# wirelessSensor_0_1.net
KiCad netlist of a schematic drawn in EAGLE
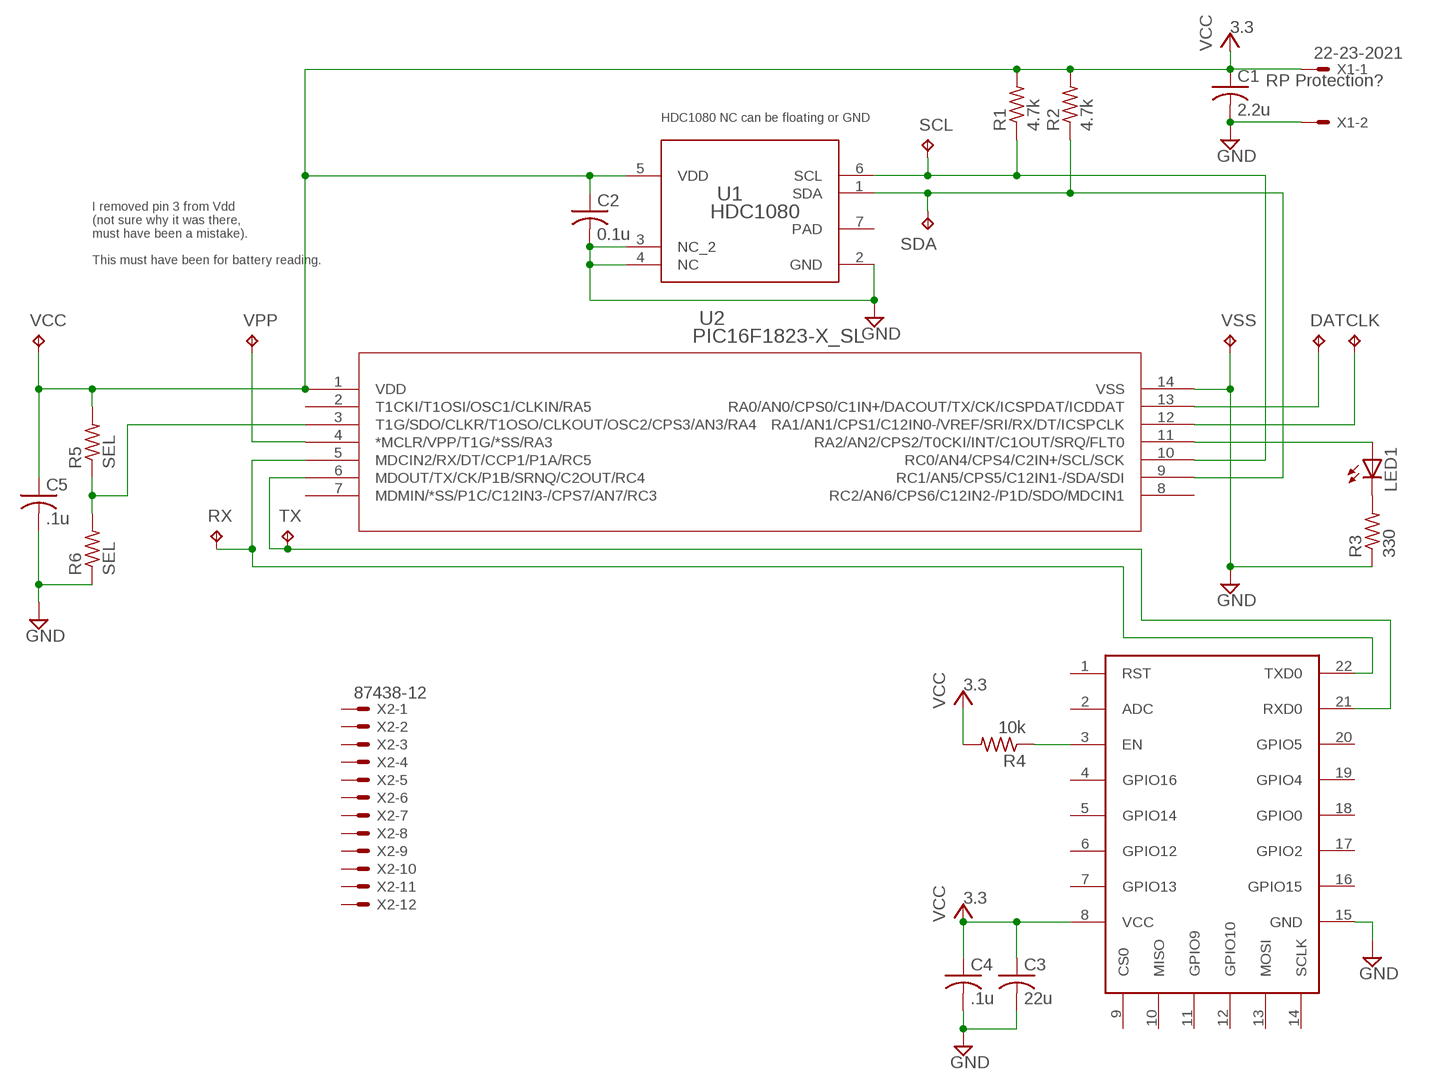
[diagram p0: schematic, sheet 1]

(export (version "E")
  (design (tool "Eeschema 10.0.6"))
  (components
    (comp (ref "C1")
      (value "2.2u")
      (footprint "eagle-import:C0603")
      (libsource (lib "eagle-import") (part "C-USC0603"))
    )
    (comp (ref "C2")
      (value "0.1u")
      (footprint "eagle-import:C0603")
      (libsource (lib "eagle-import") (part "C-USC0603"))
    )
    (comp (ref "C3")
      (value "22u")
      (footprint "eagle-import:C0603K")
      (libsource (lib "eagle-import") (part "C-USC0603K"))
    )
    (comp (ref "C4")
      (value ".1u")
      (footprint "eagle-import:C0603K")
      (libsource (lib "eagle-import") (part "C-USC0603K"))
    )
    (comp (ref "C5")
      (value ".1u")
      (footprint "eagle-import:C0603K")
      (libsource (lib "eagle-import") (part "C-USC0603K"))
    )
    (comp (ref "CLK")
      (value "TPB1,27")
      (footprint "eagle-import:B1,27")
      (libsource (lib "eagle-import") (part "TPB1,27"))
    )
    (comp (ref "DAT")
      (value "TPB1,27")
      (footprint "eagle-import:B1,27")
      (libsource (lib "eagle-import") (part "TPB1,27"))
    )
    (comp (ref "LED1")
      (value "LEDCHIP-LED0603")
      (footprint "eagle-import:CHIP-LED0603")
      (libsource (lib "eagle-import") (part "LEDCHIP-LED0603"))
    )
    (comp (ref "R1")
      (value "4.7k")
      (footprint "eagle-import:R0603")
      (libsource (lib "eagle-import") (part "R-US_R0603"))
    )
    (comp (ref "R2")
      (value "4.7k")
      (footprint "eagle-import:R0603")
      (libsource (lib "eagle-import") (part "R-US_R0603"))
    )
    (comp (ref "R3")
      (value "330")
      (footprint "eagle-import:R0603")
      (libsource (lib "eagle-import") (part "R-US_R0603"))
    )
    (comp (ref "R4")
      (value "10k")
      (footprint "eagle-import:R0603")
      (libsource (lib "eagle-import") (part "R-US_R0603"))
    )
    (comp (ref "R5")
      (value "SEL")
      (footprint "eagle-import:R0603")
      (libsource (lib "eagle-import") (part "R-US_R0603"))
    )
    (comp (ref "R6")
      (value "SEL")
      (footprint "eagle-import:R0603")
      (libsource (lib "eagle-import") (part "R-US_R0603"))
    )
    (comp (ref "RX")
      (value "TPB1,27")
      (footprint "eagle-import:B1,27")
      (libsource (lib "eagle-import") (part "TPB1,27"))
    )
    (comp (ref "SCL")
      (value "TPB1,27")
      (footprint "eagle-import:B1,27")
      (libsource (lib "eagle-import") (part "TPB1,27"))
    )
    (comp (ref "SDA")
      (value "TPB1,27")
      (footprint "eagle-import:B1,27")
      (libsource (lib "eagle-import") (part "TPB1,27"))
    )
    (comp (ref "TX")
      (value "TPB1,27")
      (footprint "eagle-import:B1,27")
      (libsource (lib "eagle-import") (part "TPB1,27"))
    )
    (comp (ref "U$1")
      (value "ESP8266-12E")
      (footprint "eagle-import:ESP8266-12E")
      (libsource (lib "eagle-import") (part "ESP8266-12E"))
    )
    (comp (ref "U1")
      (value "HDC1080")
      (footprint "eagle-import:DMB0006A")
      (fields
        (field (name "ALTERNATEPARTNUMBER") "HDC1080DMBT")
        (field (name "MANUFACTURER") "Texas Instruments")
        (field (name "PARTNUMBER") "HDC1080DMBR")
      )
      (libsource (lib "eagle-import") (part "HDC1080DMBR"))
    )
    (comp (ref "U2")
      (value "PIC16F1823-X_SL")
      (footprint "eagle-import:SOIC14-N_MC")
      (libsource (lib "eagle-import") (part "PIC16F1823-X_SL"))
    )
    (comp (ref "VCC")
      (value "TPB1,27")
      (footprint "eagle-import:B1,27")
      (libsource (lib "eagle-import") (part "TPB1,27"))
    )
    (comp (ref "VPP")
      (value "TPB1,27")
      (footprint "eagle-import:B1,27")
      (libsource (lib "eagle-import") (part "TPB1,27"))
    )
    (comp (ref "VSS")
      (value "TPB1,27")
      (footprint "eagle-import:B1,27")
      (libsource (lib "eagle-import") (part "TPB1,27"))
    )
    (comp (ref "X1")
      (value "22-23-2021")
      (footprint "eagle-import:22-23-2021")
      (fields (field (name "MF") "MOLEX"))
      (libsource (lib "eagle-import") (part "22-23-2021"))
    )
    (comp (ref "X2")
      (value "87438-12")
      (footprint "eagle-import:87438-12")
      (libsource (lib "eagle-import") (part "87438-12"))
    )
  )
  (nets
    (net (code "1") (name "/PAD") (class "Default")
      (node (ref "U1") (pin "7") (pinfunction "PAD_7") (pintype "power_in"))
    )
    (net (code "2") (name "GND") (class "Default")
      (node (ref "C1") (pin "2") (pinfunction "2_2") (pintype "passive"))
      (node (ref "C2") (pin "2") (pinfunction "2_2") (pintype "passive"))
      (node (ref "C3") (pin "2") (pinfunction "2_2") (pintype "passive"))
      (node (ref "C4") (pin "2") (pinfunction "2_2") (pintype "passive"))
      (node (ref "C5") (pin "2") (pinfunction "2_2") (pintype "passive"))
      (node (ref "R3") (pin "1") (pinfunction "1_1") (pintype "passive"))
      (node (ref "R6") (pin "1") (pinfunction "1_1") (pintype "passive"))
      (node (ref "U$1") (pin "15") (pinfunction "GND_15") (pintype "power_in"))
      (node (ref "U1") (pin "2") (pinfunction "GND_2") (pintype "power_in"))
      (node (ref "U1") (pin "3") (pinfunction "NC_2_3") (pintype "passive"))
      (node (ref "U1") (pin "4") (pinfunction "NC_4") (pintype "passive"))
      (node (ref "U2") (pin "14") (pinfunction "VSS_14") (pintype "power_in"))
      (node (ref "VSS") (pin "TP") (pinfunction "TP_TP") (pintype "input"))
      (node (ref "X1") (pin "2") (pinfunction "S_2") (pintype "passive"))
    )
    (net (code "3") (name "Net-(LED1-PadC)") (class "Default")
      (node (ref "LED1") (pin "C") (pinfunction "C_C") (pintype "passive"))
      (node (ref "R3") (pin "2") (pinfunction "2_2") (pintype "passive"))
    )
    (net (code "4") (name "Net-(U$1-EN)") (class "Default")
      (node (ref "R4") (pin "1") (pinfunction "1_1") (pintype "passive"))
      (node (ref "U$1") (pin "3") (pinfunction "EN_3") (pintype "input"))
    )
    (net (code "5") (name "Net-(U$1-RXD0)") (class "Default")
      (node (ref "TX") (pin "TP") (pinfunction "TP_TP") (pintype "input"))
      (node (ref "U$1") (pin "21") (pinfunction "RXD0_21") (pintype "input"))
      (node (ref "U2") (pin "6") (pinfunction "MDOUT/TX/CK/P1B/SRNQ/C2OUT/RC4_6") (pintype "bidirectional"))
    )
    (net (code "6") (name "Net-(U$1-TXD0)") (class "Default")
      (node (ref "RX") (pin "TP") (pinfunction "TP_TP") (pintype "input"))
      (node (ref "U$1") (pin "22") (pinfunction "TXD0_22") (pintype "output"))
      (node (ref "U2") (pin "5") (pinfunction "MDCIN2/RX/DT/CCP1/P1A/RC5_5") (pintype "bidirectional"))
    )
    (net (code "7") (name "Net-(U1-SCL)") (class "Default")
      (node (ref "R1") (pin "1") (pinfunction "1_1") (pintype "passive"))
      (node (ref "SCL") (pin "TP") (pinfunction "TP_TP") (pintype "input"))
      (node (ref "U1") (pin "6") (pinfunction "SCL_6") (pintype "open_collector"))
      (node (ref "U2") (pin "10") (pinfunction "RC0/AN4/CPS4/C2IN+/SCL/SCK_10") (pintype "bidirectional"))
    )
    (net (code "8") (name "Net-(U1-SDA)") (class "Default")
      (node (ref "R2") (pin "1") (pinfunction "1_1") (pintype "passive"))
      (node (ref "SDA") (pin "TP") (pinfunction "TP_TP") (pintype "input"))
      (node (ref "U1") (pin "1") (pinfunction "SDA_1") (pintype "bidirectional"))
      (node (ref "U2") (pin "9") (pinfunction "RC1/AN5/CPS5/C12IN1-/SDA/SDI_9") (pintype "bidirectional"))
    )
    (net (code "9") (name "Net-(U2-*MCLR{slash}VPP{slash}T1G{slash}*SS{slash}RA3)") (class "Default")
      (node (ref "U2") (pin "4") (pinfunction "*MCLR/VPP/T1G/*SS/RA3_4") (pintype "bidirectional"))
      (node (ref "VPP") (pin "TP") (pinfunction "TP_TP") (pintype "input"))
    )
    (net (code "10") (name "Net-(U2-RA0{slash}AN0{slash}CPS0{slash}C1IN+{slash}DACOUT{slash}TX{slash}CK{slash}ICSPDAT{slash}ICDDAT)") (class "Default")
      (node (ref "DAT") (pin "TP") (pinfunction "TP_TP") (pintype "input"))
      (node (ref "U2") (pin "13") (pinfunction "RA0/AN0/CPS0/C1IN+/DACOUT/TX/CK/ICSPDAT/ICDDAT_13") (pintype "bidirectional"))
    )
    (net (code "11") (name "Net-(U2-RA1{slash}AN1{slash}CPS1{slash}C12IN0-{slash}VREF{slash}SRI{slash}RX{slash}DT{slash}ICSPCLK)") (class "Default")
      (node (ref "CLK") (pin "TP") (pinfunction "TP_TP") (pintype "input"))
      (node (ref "U2") (pin "12") (pinfunction "RA1/AN1/CPS1/C12IN0-/VREF/SRI/RX/DT/ICSPCLK_12") (pintype "bidirectional"))
    )
    (net (code "12") (name "Net-(U2-RA2{slash}AN2{slash}CPS2{slash}T0CKI{slash}INT{slash}C1OUT{slash}SRQ{slash}FLT0)") (class "Default")
      (node (ref "LED1") (pin "A") (pinfunction "A_A") (pintype "passive"))
      (node (ref "U2") (pin "11") (pinfunction "RA2/AN2/CPS2/T0CKI/INT/C1OUT/SRQ/FLT0_11") (pintype "bidirectional"))
    )
    (net (code "13") (name "Net-(U2-T1G{slash}SDO{slash}CLKR{slash}T1OSO{slash}CLKOUT{slash}OSC2{slash}CPS3{slash}AN3{slash}RA4)") (class "Default")
      (node (ref "R5") (pin "1") (pinfunction "1_1") (pintype "passive"))
      (node (ref "R6") (pin "2") (pinfunction "2_2") (pintype "passive"))
      (node (ref "U2") (pin "3") (pinfunction "T1G/SDO/CLKR/T1OSO/CLKOUT/OSC2/CPS3/AN3/RA4_3") (pintype "bidirectional"))
    )
    (net (code "14") (name "VCC") (class "Default")
      (node (ref "C1") (pin "1") (pinfunction "1_1") (pintype "passive"))
      (node (ref "C2") (pin "1") (pinfunction "1_1") (pintype "passive"))
      (node (ref "C3") (pin "1") (pinfunction "1_1") (pintype "passive"))
      (node (ref "C4") (pin "1") (pinfunction "1_1") (pintype "passive"))
      (node (ref "C5") (pin "1") (pinfunction "1_1") (pintype "passive"))
      (node (ref "R1") (pin "2") (pinfunction "2_2") (pintype "passive"))
      (node (ref "R2") (pin "2") (pinfunction "2_2") (pintype "passive"))
      (node (ref "R4") (pin "2") (pinfunction "2_2") (pintype "passive"))
      (node (ref "R5") (pin "2") (pinfunction "2_2") (pintype "passive"))
      (node (ref "U$1") (pin "8") (pinfunction "VCC_8") (pintype "power_in"))
      (node (ref "U1") (pin "5") (pinfunction "VDD_5") (pintype "power_in"))
      (node (ref "U2") (pin "1") (pinfunction "VDD_1") (pintype "power_in"))
      (node (ref "VCC") (pin "TP") (pinfunction "TP_TP") (pintype "input"))
      (node (ref "X1") (pin "1") (pinfunction "S_1") (pintype "passive"))
    )
    (net (code "15") (name "unconnected-(U$1-ADC-Pad2)") (class "Default")
      (node (ref "U$1") (pin "2") (pinfunction "ADC_2") (pintype "input"))
    )
    (net (code "16") (name "unconnected-(U$1-CS0-Pad9)") (class "Default")
      (node (ref "U$1") (pin "9") (pinfunction "CS0_9") (pintype "bidirectional"))
    )
    (net (code "17") (name "unconnected-(U$1-GPIO0-Pad18)") (class "Default")
      (node (ref "U$1") (pin "18") (pinfunction "GPIO0_18") (pintype "bidirectional"))
    )
    (net (code "18") (name "unconnected-(U$1-GPIO2-Pad17)") (class "Default")
      (node (ref "U$1") (pin "17") (pinfunction "GPIO2_17") (pintype "bidirectional"))
    )
    (net (code "19") (name "unconnected-(U$1-GPIO4-Pad19)") (class "Default")
      (node (ref "U$1") (pin "19") (pinfunction "GPIO4_19") (pintype "bidirectional"))
    )
    (net (code "20") (name "unconnected-(U$1-GPIO5-Pad20)") (class "Default")
      (node (ref "U$1") (pin "20") (pinfunction "GPIO5_20") (pintype "bidirectional"))
    )
    (net (code "21") (name "unconnected-(U$1-GPIO9-Pad11)") (class "Default")
      (node (ref "U$1") (pin "11") (pinfunction "GPIO9_11") (pintype "bidirectional"))
    )
    (net (code "22") (name "unconnected-(U$1-GPIO10-Pad12)") (class "Default")
      (node (ref "U$1") (pin "12") (pinfunction "GPIO10_12") (pintype "bidirectional"))
    )
    (net (code "23") (name "unconnected-(U$1-GPIO12-Pad6)") (class "Default")
      (node (ref "U$1") (pin "6") (pinfunction "GPIO12_6") (pintype "bidirectional"))
    )
    (net (code "24") (name "unconnected-(U$1-GPIO13-Pad7)") (class "Default")
      (node (ref "U$1") (pin "7") (pinfunction "GPIO13_7") (pintype "bidirectional"))
    )
    (net (code "25") (name "unconnected-(U$1-GPIO14-Pad5)") (class "Default")
      (node (ref "U$1") (pin "5") (pinfunction "GPIO14_5") (pintype "bidirectional"))
    )
    (net (code "26") (name "unconnected-(U$1-GPIO15-Pad16)") (class "Default")
      (node (ref "U$1") (pin "16") (pinfunction "GPIO15_16") (pintype "bidirectional"))
    )
    (net (code "27") (name "unconnected-(U$1-GPIO16-Pad4)") (class "Default")
      (node (ref "U$1") (pin "4") (pinfunction "GPIO16_4") (pintype "bidirectional"))
    )
    (net (code "28") (name "unconnected-(U$1-MISO-Pad10)") (class "Default")
      (node (ref "U$1") (pin "10") (pinfunction "MISO_10") (pintype "bidirectional"))
    )
    (net (code "29") (name "unconnected-(U$1-MOSI-Pad13)") (class "Default")
      (node (ref "U$1") (pin "13") (pinfunction "MOSI_13") (pintype "bidirectional"))
    )
    (net (code "30") (name "unconnected-(U$1-RST-Pad1)") (class "Default")
      (node (ref "U$1") (pin "1") (pinfunction "RST_1") (pintype "input"))
    )
    (net (code "31") (name "unconnected-(U$1-SCLK-Pad14)") (class "Default")
      (node (ref "U$1") (pin "14") (pinfunction "SCLK_14") (pintype "bidirectional"))
    )
    (net (code "32") (name "unconnected-(U2-MDMIN{slash}*SS{slash}P1C{slash}C12IN3-{slash}CPS7{slash}AN7{slash}RC3-Pad7)") (class "Default")
      (node (ref "U2") (pin "7") (pinfunction "MDMIN/*SS/P1C/C12IN3-/CPS7/AN7/RC3_7") (pintype "bidirectional"))
    )
    (net (code "33") (name "unconnected-(U2-RC2{slash}AN6{slash}CPS6{slash}C12IN2-{slash}P1D{slash}SDO{slash}MDCIN1-Pad8)") (class "Default")
      (node (ref "U2") (pin "8") (pinfunction "RC2/AN6/CPS6/C12IN2-/P1D/SDO/MDCIN1_8") (pintype "bidirectional"))
    )
    (net (code "34") (name "unconnected-(U2-T1CKI{slash}T1OSI{slash}OSC1{slash}CLKIN{slash}RA5-Pad2)") (class "Default")
      (node (ref "U2") (pin "2") (pinfunction "T1CKI/T1OSI/OSC1/CLKIN/RA5_2") (pintype "bidirectional"))
    )
    (net (code "35") (name "unconnected-(X2A-S-Pad1)") (class "Default")
      (node (ref "X2") (pin "1") (pinfunction "S_1") (pintype "passive"))
    )
    (net (code "36") (name "unconnected-(X2B-S-Pad10)") (class "Default")
      (node (ref "X2") (pin "10") (pinfunction "S_10") (pintype "passive"))
    )
    (net (code "37") (name "unconnected-(X2C-S-Pad11)") (class "Default")
      (node (ref "X2") (pin "11") (pinfunction "S_11") (pintype "passive"))
    )
    (net (code "38") (name "unconnected-(X2D-S-Pad12)") (class "Default")
      (node (ref "X2") (pin "12") (pinfunction "S_12") (pintype "passive"))
    )
    (net (code "39") (name "unconnected-(X2E-S-Pad2)") (class "Default")
      (node (ref "X2") (pin "2") (pinfunction "S_2") (pintype "passive"))
    )
    (net (code "40") (name "unconnected-(X2F-S-Pad3)") (class "Default")
      (node (ref "X2") (pin "3") (pinfunction "S_3") (pintype "passive"))
    )
    (net (code "41") (name "unconnected-(X2G-S-Pad4)") (class "Default")
      (node (ref "X2") (pin "4") (pinfunction "S_4") (pintype "passive"))
    )
    (net (code "42") (name "unconnected-(X2H-S-Pad5)") (class "Default")
      (node (ref "X2") (pin "5") (pinfunction "S_5") (pintype "passive"))
    )
    (net (code "43") (name "unconnected-(X2I-S-Pad6)") (class "Default")
      (node (ref "X2") (pin "6") (pinfunction "S_6") (pintype "passive"))
    )
    (net (code "44") (name "unconnected-(X2J-S-Pad7)") (class "Default")
      (node (ref "X2") (pin "7") (pinfunction "S_7") (pintype "passive"))
    )
    (net (code "45") (name "unconnected-(X2K-S-Pad8)") (class "Default")
      (node (ref "X2") (pin "8") (pinfunction "S_8") (pintype "passive"))
    )
    (net (code "46") (name "unconnected-(X2L-S-Pad9)") (class "Default")
      (node (ref "X2") (pin "9") (pinfunction "S_9") (pintype "passive"))
    )
  )
)
